# ProProject_12v_5v__2024-07-26.net
KiCad netlist of a schematic drawn in EasyEDA Pro
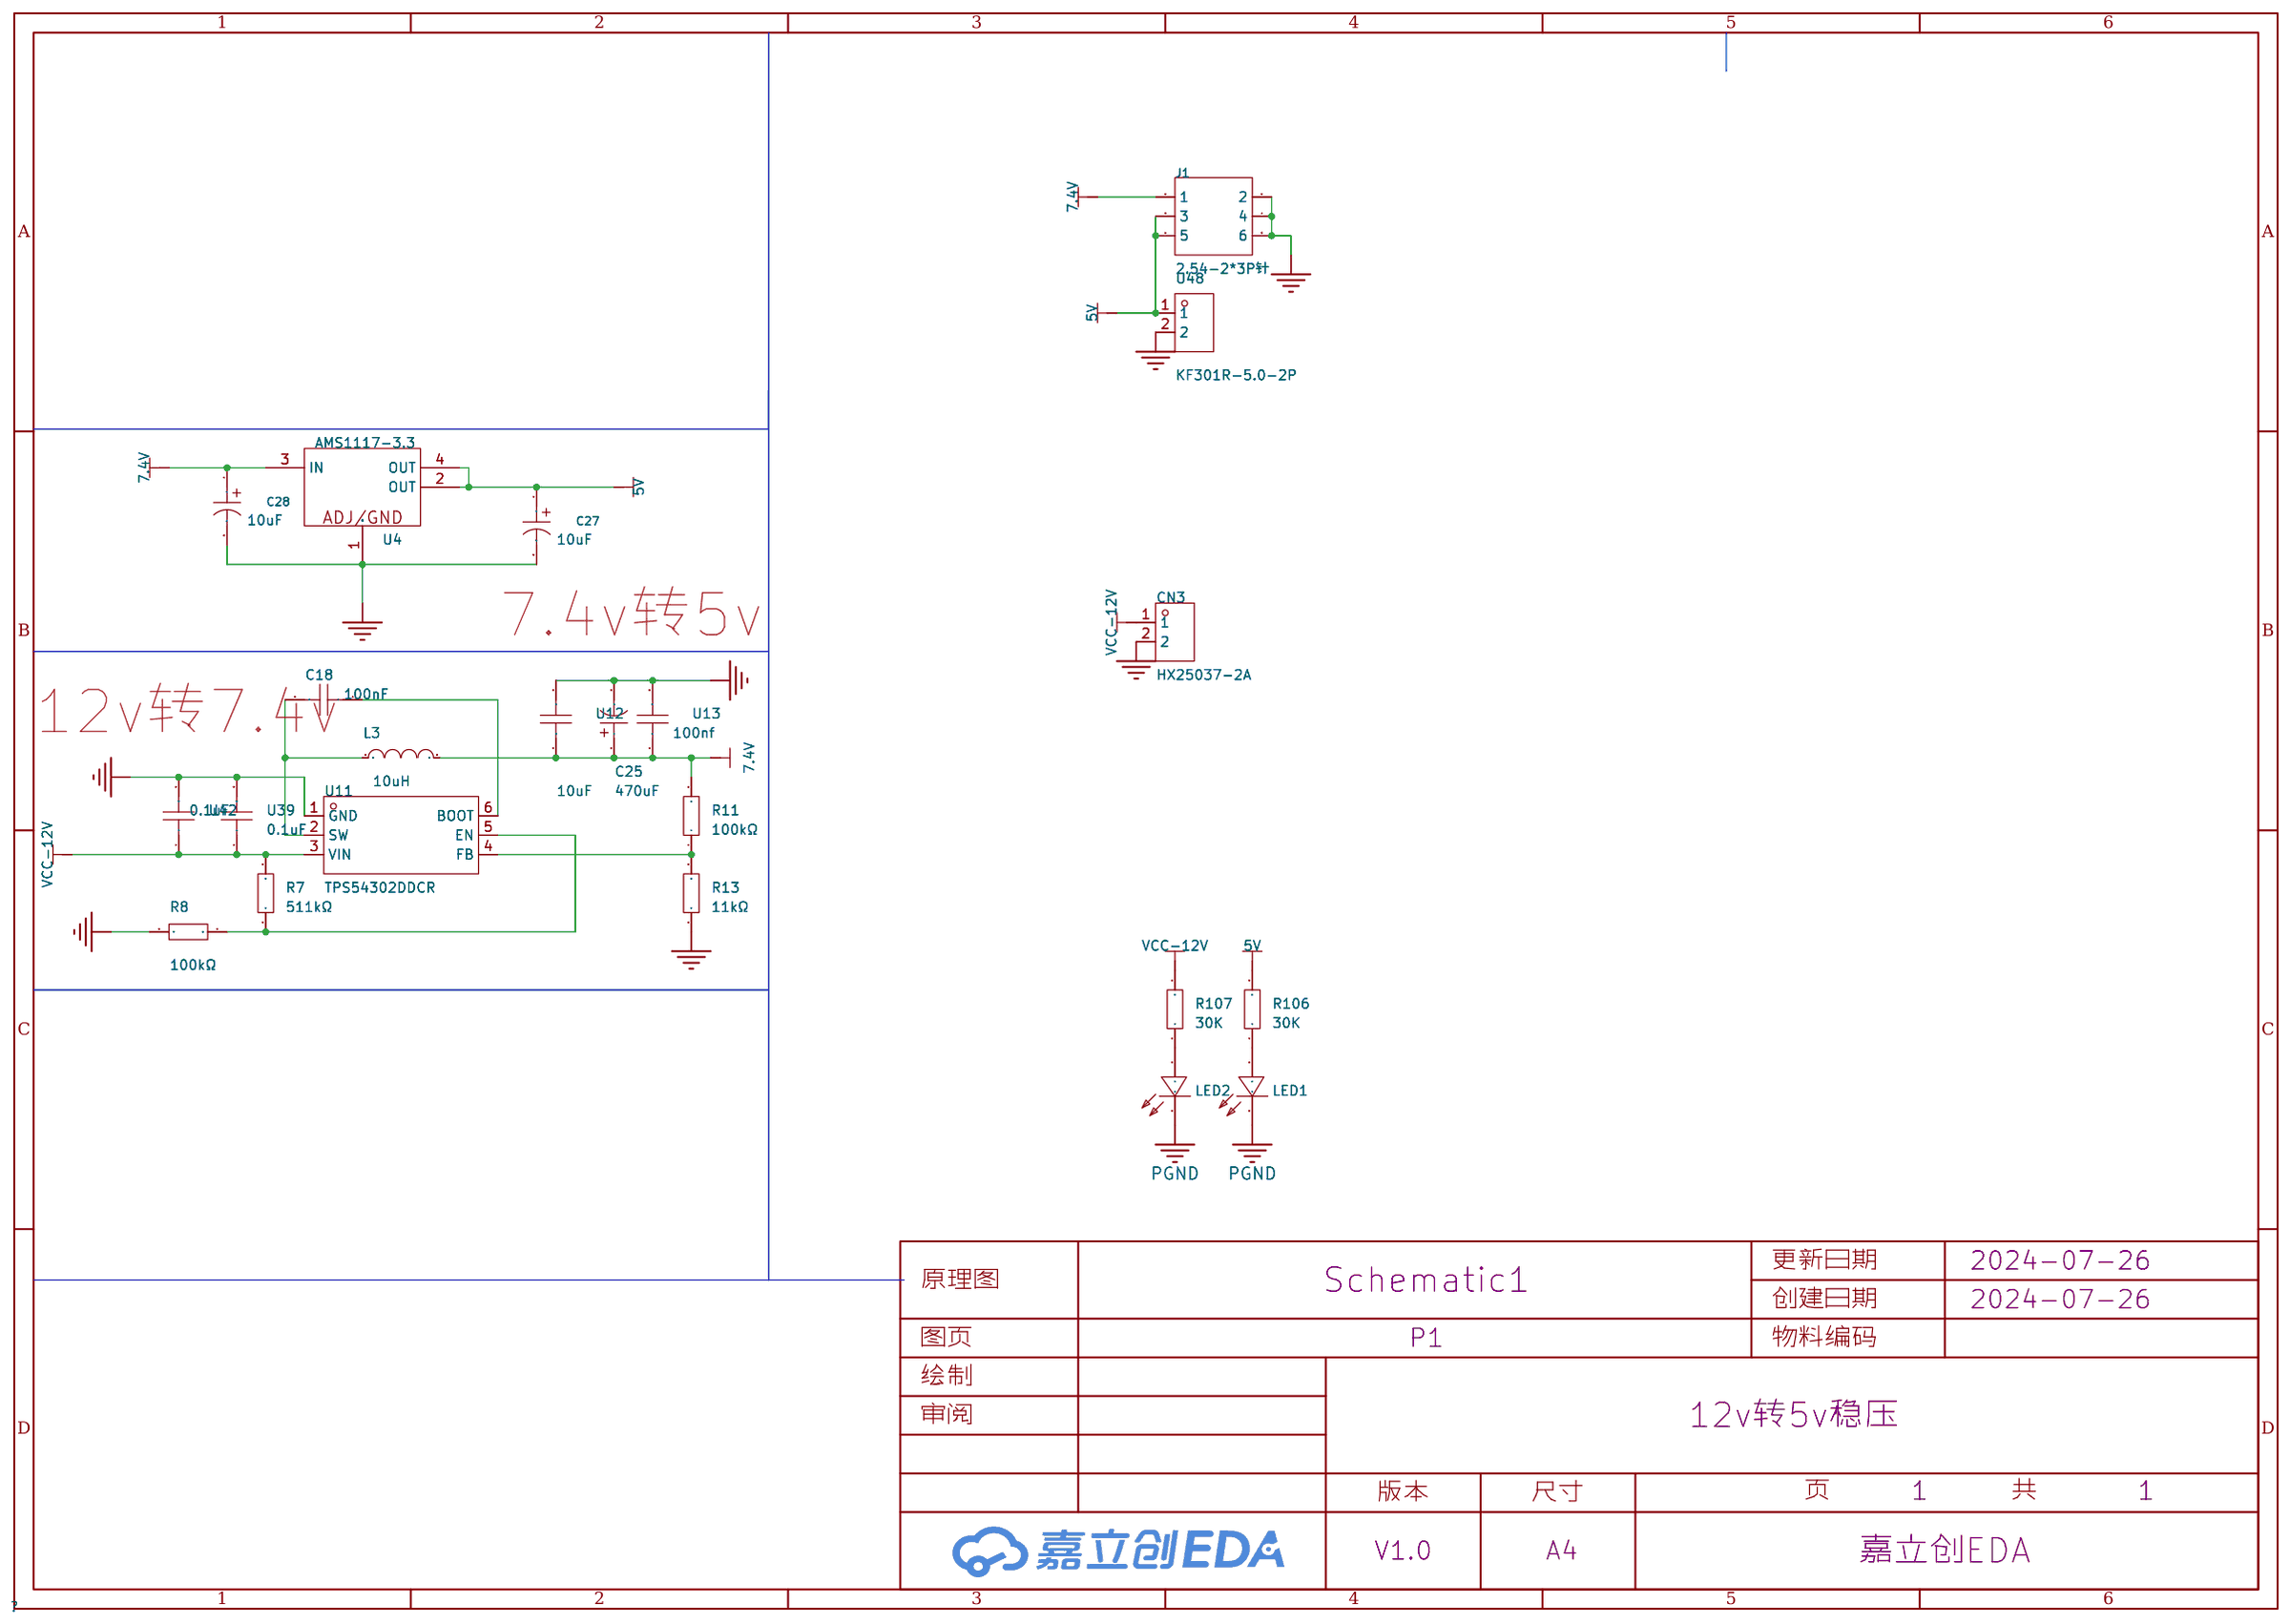
[diagram p0: schematic sheet]

(export (version "E")
  (design (tool "Eeschema 10.0.6"))
  (components
    (comp (ref "C18")
      (value "100nF")
      (footprint "easyedapro:C0603")
      (description "容值:100nF;精度:±10%;额定电压:50V;材质(温度系数):X7R;")
      (fields
        (field (name "Manufacturer Part") "CC0603KRX7R9BB104")
        (field (name "Manufacturer") "YAGEO(国巨)")
      )
      (libsource (lib "easyedapro") (part "CC0603KRX7R9BB104"))
    )
    (comp (ref "C25")
      (value "470uF")
      (footprint "easyedapro:CAP-SMD_BD10.0-L10.3-W10.3-LS11.3-FD")
      (description "容值:470uF;额定电压:35V;电容体直径:-;电容体长度:-;纹波电流:-;等效串联电阻:-;工作寿命:-;")
      (fields
        (field (name "Manufacturer Part") "XT470UF35V90RV0080")
        (field (name "Manufacturer") "KNSCHA(科尼盛)")
      )
      (libsource (lib "easyedapro") (part "XT470UF35V90RV0080"))
    )
    (comp (ref "C27")
      (value "10uF")
      (footprint "easyedapro:CAP-SMD_L1.6-W0.9-FD")
      (description "容值:10uF;精度:±20%;额定电压:10V;等效串联电阻:9Ω;")
      (fields (field (name "Manufacturer Part") "TCM1A106M8R") (field (name "Manufacturer") "ROHM(罗姆)"))
      (libsource (lib "easyedapro") (part "TCM1A106M8R"))
    )
    (comp (ref "C28")
      (value "10uF")
      (footprint "easyedapro:CAP-SMD_L1.6-W0.9-FD")
      (description "容值:10uF;精度:±20%;额定电压:10V;等效串联电阻:9Ω;")
      (fields (field (name "Manufacturer Part") "TCM1A106M8R") (field (name "Manufacturer") "ROHM(罗姆)"))
      (libsource (lib "easyedapro") (part "TCM1A106M8R"))
    )
    (comp (ref "CN3")
      (value "HX25037-2A")
      (footprint "easyedapro:CONN-TH_2P-P2.50-XH2.54-2P")
      (libsource (lib "easyedapro") (part "HX25037-2A_C9900012767"))
    )
    (comp (ref "J1")
      (value "2.54-2*3P针")
      (footprint "easyedapro:HDR-TH_6P-P2.54-V-M-R2-C3-S2.54-1")
      (fields (field (name "Manufacturer") "BOOMELE(博穆精密)"))
      (libsource (lib "easyedapro") (part "Header-Male-2.54_2x3"))
    )
    (comp (ref "L3")
      (value "10uH")
      (footprint "easyedapro:IND-SMD_L5.4-W5.2_FXL0530")
      (description "电感值:4.7uH;精度:±20%;额定电流:4.5A;饱和电流(Isat):5A;直流电阻(DCR):50mΩ;")
      (fields (field (name "Manufacturer Part") "FXL0530-4R7-M") (field (name "Manufacturer") "cjiang(长江微电)"))
      (libsource (lib "easyedapro") (part "FXL0530-4R7-M"))
    )
    (comp (ref "LED1")
      (value "NCD0603R3")
      (footprint "easyedapro:LED0603-R-RD_RED")
      (description "尺寸1.6x0.8x0.8；IF=20ma：1.6~2.6v，620~640nm,51~150mcd金线，光强高，功耗低，可靠性好，寿命长")
      (fields (field (name "Manufacturer") "国星光电"))
      (libsource (lib "easyedapro") (part "NCD0603R3"))
    )
    (comp (ref "LED2")
      (value "NCD0603R3")
      (footprint "easyedapro:LED0603-R-RD_RED")
      (description "尺寸1.6x0.8x0.8；IF=20ma：1.6~2.6v，620~640nm,51~150mcd金线，光强高，功耗低，可靠性好，寿命长")
      (fields (field (name "Manufacturer") "国星光电"))
      (libsource (lib "easyedapro") (part "NCD0603R3"))
    )
    (comp (ref "R7")
      (value "511kΩ")
      (footprint "easyedapro:R0603")
      (description "电阻类型:厚膜电阻;阻值:511kΩ;精度:±1%;功率:100mW;最大工作电压:50V;温度系数:±100ppm/°C;")
      (fields (field (name "Manufacturer Part") "RS-03K5113FT") (field (name "Manufacturer") "FH(风华)"))
      (libsource (lib "easyedapro") (part "RS-03K5113FT"))
    )
    (comp (ref "R8")
      (value "100kΩ")
      (footprint "easyedapro:R0603")
      (description "电阻类型:厚膜电阻;阻值:100kΩ;精度:±1%;功率:100mW;最大工作电压:-;温度系数:±100ppm/°C;")
      (fields (field (name "Manufacturer Part") "ERJ3EKF1003V") (field (name "Manufacturer") "PANASONIC(松下)"))
      (libsource (lib "easyedapro") (part "ERJ3EKF1003V"))
    )
    (comp (ref "R11")
      (value "100kΩ")
      (footprint "easyedapro:R0603")
      (description "电阻类型:厚膜电阻;阻值:100kΩ;精度:±1%;功率:100mW;最大工作电压:75V;温度系数:±100ppm/°C;")
      (fields (field (name "Manufacturer Part") "RC0603FR-07100KL") (field (name "Manufacturer") "YAGEO(国巨)"))
      (libsource (lib "easyedapro") (part "RC0603FR-07100KL"))
    )
    (comp (ref "R13")
      (value "11kΩ")
      (footprint "easyedapro:R0603")
      (description "电阻类型:厚膜电阻;阻值:11kΩ;精度:±1%;功率:100mW;最大工作电压:75V;温度系数:±100ppm/°C;")
      (fields
        (field (name "Manufacturer Part") "0603WAF1102T5E")
        (field (name "Manufacturer") "UNI-ROYAL(厚声)")
      )
      (libsource (lib "easyedapro") (part "0603WAF1102T5E"))
    )
    (comp (ref "R106")
      (value "30K")
      (footprint "easyedapro:R0603")
      (libsource (lib "easyedapro") (part "电阻"))
    )
    (comp (ref "R107")
      (value "30K")
      (footprint "easyedapro:R0603")
      (libsource (lib "easyedapro") (part "电阻"))
    )
    (comp (ref "U4")
      (value "AMS1117-3.3")
      (footprint "easyedapro:SOT-223-3_L6.4-W3.5-P2.30-LS7.0-BR")
      (fields (field (name "Manufacturer") "国芯佳品"))
      (libsource (lib "easyedapro") (part "AMS1117-3.3_C2992570"))
    )
    (comp (ref "U11")
      (value "TPS54302DDCR")
      (footprint "easyedapro:SOT-23-6_L2.9-W1.6-P0.95-LS2.8-BL")
      (description "功能类型:降压型;输出类型:可调;输入电压:4.5V~28V;输出电压:596mV~28V;输出电流(最大值):3A;")
      (fields (field (name "Manufacturer") "TI(德州仪器)"))
      (libsource (lib "easyedapro") (part "TPS54302DDCR_C311983"))
    )
    (comp (ref "U12")
      (value "10uF")
      (footprint "easyedapro:C0603")
      (description "容值:22uF;精度:±20%;额定电压:4V;材质(温度系数):X5R;")
      (fields
        (field (name "Manufacturer Part") "GRM188R60G226MEA0D")
        (field (name "Manufacturer") "muRata(村田)")
      )
      (libsource (lib "easyedapro") (part "GRM188R60G226MEA0D"))
    )
    (comp (ref "U13")
      (value "100nf")
      (footprint "easyedapro:C0603")
      (description "容值:22uF;精度:±20%;额定电压:4V;材质(温度系数):X5R;")
      (fields
        (field (name "Manufacturer Part") "GRM188R60G226MEA0D")
        (field (name "Manufacturer") "muRata(村田)")
      )
      (libsource (lib "easyedapro") (part "GRM188R60G226MEA0D"))
    )
    (comp (ref "U39")
      (value "0.1uF")
      (footprint "easyedapro:C0603")
      (description "容值:22uF;精度:±20%;额定电压:4V;材质(温度系数):X5R;")
      (fields
        (field (name "Manufacturer Part") "GRM188R60G226MEA0D")
        (field (name "Manufacturer") "muRata(村田)")
      )
      (libsource (lib "easyedapro") (part "GRM188R60G226MEA0D"))
    )
    (comp (ref "U42")
      (value "0.1uF")
      (footprint "easyedapro:C0603")
      (description "容值:22uF;精度:±20%;额定电压:4V;材质(温度系数):X5R;")
      (fields
        (field (name "Manufacturer Part") "GRM188R60G226MEA0D")
        (field (name "Manufacturer") "muRata(村田)")
      )
      (libsource (lib "easyedapro") (part "GRM188R60G226MEA0D"))
    )
    (comp (ref "U48")
      (value "KF301R-5.0-2P")
      (footprint "easyedapro:CONN-TH_P5.00_KF301R-5.0-2P")
      (fields (field (name "Manufacturer") "KEFA(科发)"))
      (libsource (lib "easyedapro") (part "KF301R-5.0-2P"))
    )
  )
  (nets
    (net (code "1") (name "5V") (class "Default")
      (node (ref "C27") (pin "1") (pinfunction "1_1") (pintype "input"))
      (node (ref "J1") (pin "3") (pinfunction "3_3") (pintype "input"))
      (node (ref "J1") (pin "5") (pinfunction "5_5") (pintype "input"))
      (node (ref "R106") (pin "2") (pinfunction "2_2") (pintype "input"))
      (node (ref "U4") (pin "2") (pinfunction "OUT_2") (pintype "input"))
      (node (ref "U4") (pin "4") (pinfunction "OUT_4") (pintype "input"))
      (node (ref "U48") (pin "1") (pinfunction "1_1") (pintype "unspecified"))
    )
    (net (code "2") (name "7.4V") (class "Default")
      (node (ref "C25") (pin "1") (pinfunction "1_1") (pintype "input"))
      (node (ref "C28") (pin "1") (pinfunction "1_1") (pintype "input"))
      (node (ref "J1") (pin "1") (pinfunction "1_1") (pintype "input"))
      (node (ref "L3") (pin "2") (pinfunction "2_2") (pintype "input"))
      (node (ref "R11") (pin "2") (pinfunction "2_2") (pintype "unspecified"))
      (node (ref "U12") (pin "1") (pinfunction "1_1") (pintype "input"))
      (node (ref "U13") (pin "1") (pinfunction "1_1") (pintype "input"))
      (node (ref "U4") (pin "3") (pinfunction "IN_3") (pintype "input"))
    )
    (net (code "3") (name "GND") (class "Default")
      (node (ref "CN3") (pin "2") (pinfunction "2_2") (pintype "input"))
    )
    (net (code "4") (name "Net-(LED1-A)") (class "Default")
      (node (ref "LED1") (pin "1") (pinfunction "A_1") (pintype "input"))
      (node (ref "R106") (pin "1") (pinfunction "1_1") (pintype "input"))
    )
    (net (code "5") (name "Net-(LED2-A)") (class "Default")
      (node (ref "LED2") (pin "1") (pinfunction "A_1") (pintype "input"))
      (node (ref "R107") (pin "1") (pinfunction "1_1") (pintype "input"))
    )
    (net (code "6") (name "Net-(U11-BOOT)") (class "Default")
      (node (ref "C18") (pin "1") (pinfunction "1_1") (pintype "input"))
      (node (ref "U11") (pin "6") (pinfunction "BOOT_6") (pintype "input"))
    )
    (net (code "7") (name "Net-(U11-EN)") (class "Default")
      (node (ref "R7") (pin "1") (pinfunction "1_1") (pintype "unspecified"))
      (node (ref "R8") (pin "1") (pinfunction "1_1") (pintype "unspecified"))
      (node (ref "U11") (pin "5") (pinfunction "EN_5") (pintype "input"))
    )
    (net (code "8") (name "Net-(U11-FB)") (class "Default")
      (node (ref "R11") (pin "1") (pinfunction "1_1") (pintype "unspecified"))
      (node (ref "R13") (pin "2") (pinfunction "2_2") (pintype "input"))
      (node (ref "U11") (pin "4") (pinfunction "FB_4") (pintype "input"))
    )
    (net (code "9") (name "Net-(U11-SW)") (class "Default")
      (node (ref "C18") (pin "2") (pinfunction "2_2") (pintype "input"))
      (node (ref "L3") (pin "1") (pinfunction "1_1") (pintype "input"))
      (node (ref "U11") (pin "2") (pinfunction "SW_2") (pintype "input"))
    )
    (net (code "10") (name "PGND") (class "Default")
      (node (ref "C25") (pin "2") (pinfunction "2_2") (pintype "input"))
      (node (ref "C27") (pin "2") (pinfunction "2_2") (pintype "input"))
      (node (ref "C28") (pin "2") (pinfunction "2_2") (pintype "input"))
      (node (ref "J1") (pin "2") (pinfunction "2_2") (pintype "input"))
      (node (ref "J1") (pin "4") (pinfunction "4_4") (pintype "input"))
      (node (ref "J1") (pin "6") (pinfunction "6_6") (pintype "input"))
      (node (ref "LED1") (pin "2") (pinfunction "K_2") (pintype "input"))
      (node (ref "LED2") (pin "2") (pinfunction "K_2") (pintype "input"))
      (node (ref "R13") (pin "1") (pinfunction "1_1") (pintype "input"))
      (node (ref "R8") (pin "2") (pinfunction "2_2") (pintype "unspecified"))
      (node (ref "U11") (pin "1") (pinfunction "GND_1") (pintype "input"))
      (node (ref "U12") (pin "2") (pinfunction "2_2") (pintype "input"))
      (node (ref "U13") (pin "2") (pinfunction "2_2") (pintype "input"))
      (node (ref "U39") (pin "2") (pinfunction "2_2") (pintype "input"))
      (node (ref "U4") (pin "1") (pinfunction "ADJ/GND_1") (pintype "input"))
      (node (ref "U42") (pin "2") (pinfunction "2_2") (pintype "input"))
      (node (ref "U48") (pin "2") (pinfunction "2_2") (pintype "unspecified"))
    )
    (net (code "11") (name "VCC-12V") (class "Default")
      (node (ref "CN3") (pin "1") (pinfunction "1_1") (pintype "input"))
      (node (ref "R107") (pin "2") (pinfunction "2_2") (pintype "input"))
      (node (ref "R7") (pin "2") (pinfunction "2_2") (pintype "unspecified"))
      (node (ref "U11") (pin "3") (pinfunction "VIN_3") (pintype "input"))
      (node (ref "U39") (pin "1") (pinfunction "1_1") (pintype "input"))
      (node (ref "U42") (pin "1") (pinfunction "1_1") (pintype "input"))
    )
  )
)
